# EXIST-RIP_transformerPCB.net
KiCad netlist of a schematic drawn in EAGLE
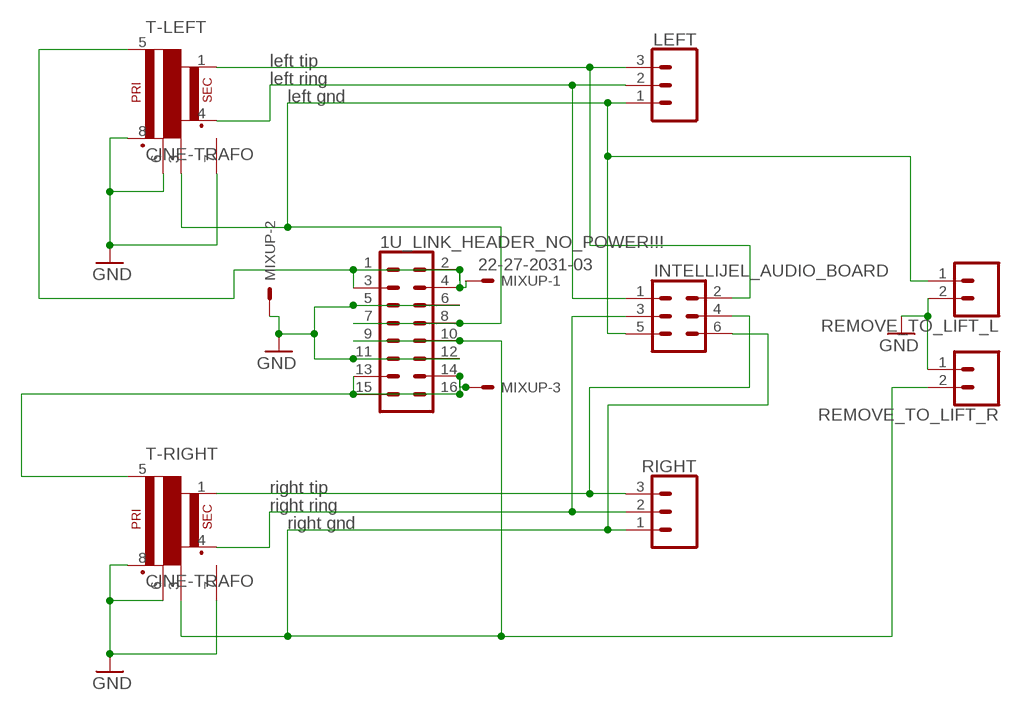
[diagram p0: schematic, sheet 1]

(export (version "E")
  (design (tool "Eeschema 10.0.6"))
  (components
    (comp (ref "1U_LINK_HEADER_NO_POWER!!!")
      (value "CONN_08X2")
      (footprint "eagle-import:2X8")
      (libsource (lib "eagle-import") (part "CONN_08X2"))
    )
    (comp (ref "INTELLIJEL_AUDIO_BOARD")
      (value "CONN_03X22X3_SILK_MALE_PTH")
      (footprint "eagle-import:2X3")
      (libsource (lib "eagle-import") (part "CONN_03X22X3_SILK_MALE_PTH"))
    )
    (comp (ref "LEFT")
      (value "CONN_03LONGPADS")
      (footprint "eagle-import:1X03_LONGPADS")
      (libsource (lib "eagle-import") (part "CONN_03LONGPADS"))
    )
    (comp (ref "MIXUP")
      (value "22-27-2031-03")
      (footprint "eagle-import:6410-03")
      (fields (field (name "MF") "MOLEX"))
      (libsource (lib "eagle-import") (part "22-?-0327-2031"))
    )
    (comp (ref "REMOVE_TO_LIFT_L")
      (value "CONN_02")
      (footprint "eagle-import:1X02")
      (libsource (lib "eagle-import") (part "CONN_02"))
    )
    (comp (ref "REMOVE_TO_LIFT_R")
      (value "CONN_02")
      (footprint "eagle-import:1X02")
      (libsource (lib "eagle-import") (part "CONN_02"))
    )
    (comp (ref "RIGHT")
      (value "CONN_03LONGPADS")
      (footprint "eagle-import:1X03_LONGPADS")
      (libsource (lib "eagle-import") (part "CONN_03LONGPADS"))
    )
    (comp (ref "T-LEFT")
      (value "CINE-TRAFO")
      (footprint "eagle-import:CIRC-TRAFO")
      (libsource (lib "eagle-import") (part "CINE-TRAFO"))
    )
    (comp (ref "T-RIGHT")
      (value "CINE-TRAFO")
      (footprint "eagle-import:CIRC-TRAFO")
      (libsource (lib "eagle-import") (part "CINE-TRAFO"))
    )
  )
  (nets
    (net (code "1") (name "GND") (class "Default")
      (node (ref "1U_LINK_HEADER_NO_POWER!!!") (pin "11") (pinfunction "11_11") (pintype "passive"))
      (node (ref "1U_LINK_HEADER_NO_POWER!!!") (pin "12") (pinfunction "12_12") (pintype "passive"))
      (node (ref "1U_LINK_HEADER_NO_POWER!!!") (pin "5") (pinfunction "5_5") (pintype "passive"))
      (node (ref "1U_LINK_HEADER_NO_POWER!!!") (pin "6") (pinfunction "6_6") (pintype "passive"))
      (node (ref "MIXUP") (pin "2") (pinfunction "S_2") (pintype "passive"))
      (node (ref "REMOVE_TO_LIFT_L") (pin "2") (pinfunction "2_2") (pintype "passive"))
      (node (ref "REMOVE_TO_LIFT_R") (pin "1") (pinfunction "1_1") (pintype "passive"))
      (node (ref "T-LEFT") (pin "6") (pinfunction "C1_6") (pintype "passive"))
      (node (ref "T-LEFT") (pin "7") (pinfunction "CASE_7") (pintype "passive"))
      (node (ref "T-LEFT") (pin "8") (pinfunction "P2_8") (pintype "passive"))
      (node (ref "T-RIGHT") (pin "6") (pinfunction "C1_6") (pintype "passive"))
      (node (ref "T-RIGHT") (pin "7") (pinfunction "CASE_7") (pintype "passive"))
      (node (ref "T-RIGHT") (pin "8") (pinfunction "P2_8") (pintype "passive"))
    )
    (net (code "2") (name "Net-(MIXUPA-S)") (class "Default")
      (node (ref "1U_LINK_HEADER_NO_POWER!!!") (pin "1") (pinfunction "1_1") (pintype "passive"))
      (node (ref "1U_LINK_HEADER_NO_POWER!!!") (pin "2") (pinfunction "2_2") (pintype "passive"))
      (node (ref "1U_LINK_HEADER_NO_POWER!!!") (pin "3") (pinfunction "3_3") (pintype "passive"))
      (node (ref "1U_LINK_HEADER_NO_POWER!!!") (pin "4") (pinfunction "4_4") (pintype "passive"))
      (node (ref "MIXUP") (pin "1") (pinfunction "S_1") (pintype "passive"))
      (node (ref "T-LEFT") (pin "5") (pinfunction "P1_5") (pintype "passive"))
    )
    (net (code "3") (name "Net-(MIXUPC-S)") (class "Default")
      (node (ref "1U_LINK_HEADER_NO_POWER!!!") (pin "13") (pinfunction "13_13") (pintype "passive"))
      (node (ref "1U_LINK_HEADER_NO_POWER!!!") (pin "14") (pinfunction "14_14") (pintype "passive"))
      (node (ref "1U_LINK_HEADER_NO_POWER!!!") (pin "15") (pinfunction "15_15") (pintype "passive"))
      (node (ref "1U_LINK_HEADER_NO_POWER!!!") (pin "16") (pinfunction "16_16") (pintype "passive"))
      (node (ref "MIXUP") (pin "3") (pinfunction "S_3") (pintype "passive"))
      (node (ref "T-RIGHT") (pin "5") (pinfunction "P1_5") (pintype "passive"))
    )
    (net (code "4") (name "Net-(T-LEFT-C2)") (class "Default")
      (node (ref "1U_LINK_HEADER_NO_POWER!!!") (pin "7") (pinfunction "7_7") (pintype "passive"))
      (node (ref "1U_LINK_HEADER_NO_POWER!!!") (pin "8") (pinfunction "8_8") (pintype "passive"))
      (node (ref "INTELLIJEL_AUDIO_BOARD") (pin "5") (pinfunction "5_5") (pintype "bidirectional"))
      (node (ref "LEFT") (pin "1") (pinfunction "1_1") (pintype "passive"))
      (node (ref "REMOVE_TO_LIFT_L") (pin "1") (pinfunction "1_1") (pintype "passive"))
      (node (ref "T-LEFT") (pin "3") (pinfunction "C2_3") (pintype "passive"))
    )
    (net (code "5") (name "Net-(T-LEFT-S1)") (class "Default")
      (node (ref "INTELLIJEL_AUDIO_BOARD") (pin "2") (pinfunction "2_2") (pintype "bidirectional"))
      (node (ref "LEFT") (pin "3") (pinfunction "3_3") (pintype "passive"))
      (node (ref "T-LEFT") (pin "1") (pinfunction "S1_1") (pintype "passive"))
    )
    (net (code "6") (name "Net-(T-LEFT-S2)") (class "Default")
      (node (ref "INTELLIJEL_AUDIO_BOARD") (pin "1") (pinfunction "1_1") (pintype "bidirectional"))
      (node (ref "LEFT") (pin "2") (pinfunction "2_2") (pintype "passive"))
      (node (ref "T-LEFT") (pin "4") (pinfunction "S2_4") (pintype "passive"))
    )
    (net (code "7") (name "Net-(T-RIGHT-C2)") (class "Default")
      (node (ref "1U_LINK_HEADER_NO_POWER!!!") (pin "10") (pinfunction "10_10") (pintype "passive"))
      (node (ref "1U_LINK_HEADER_NO_POWER!!!") (pin "9") (pinfunction "9_9") (pintype "passive"))
      (node (ref "INTELLIJEL_AUDIO_BOARD") (pin "6") (pinfunction "6_6") (pintype "bidirectional"))
      (node (ref "REMOVE_TO_LIFT_R") (pin "2") (pinfunction "2_2") (pintype "passive"))
      (node (ref "RIGHT") (pin "1") (pinfunction "1_1") (pintype "passive"))
      (node (ref "T-RIGHT") (pin "3") (pinfunction "C2_3") (pintype "passive"))
    )
    (net (code "8") (name "Net-(T-RIGHT-S1)") (class "Default")
      (node (ref "INTELLIJEL_AUDIO_BOARD") (pin "4") (pinfunction "4_4") (pintype "bidirectional"))
      (node (ref "RIGHT") (pin "3") (pinfunction "3_3") (pintype "passive"))
      (node (ref "T-RIGHT") (pin "1") (pinfunction "S1_1") (pintype "passive"))
    )
    (net (code "9") (name "Net-(T-RIGHT-S2)") (class "Default")
      (node (ref "INTELLIJEL_AUDIO_BOARD") (pin "3") (pinfunction "3_3") (pintype "bidirectional"))
      (node (ref "RIGHT") (pin "2") (pinfunction "2_2") (pintype "passive"))
      (node (ref "T-RIGHT") (pin "4") (pinfunction "S2_4") (pintype "passive"))
    )
  )
)
